# fpga.net
KiCad netlist of a schematic drawn in Altium Designer
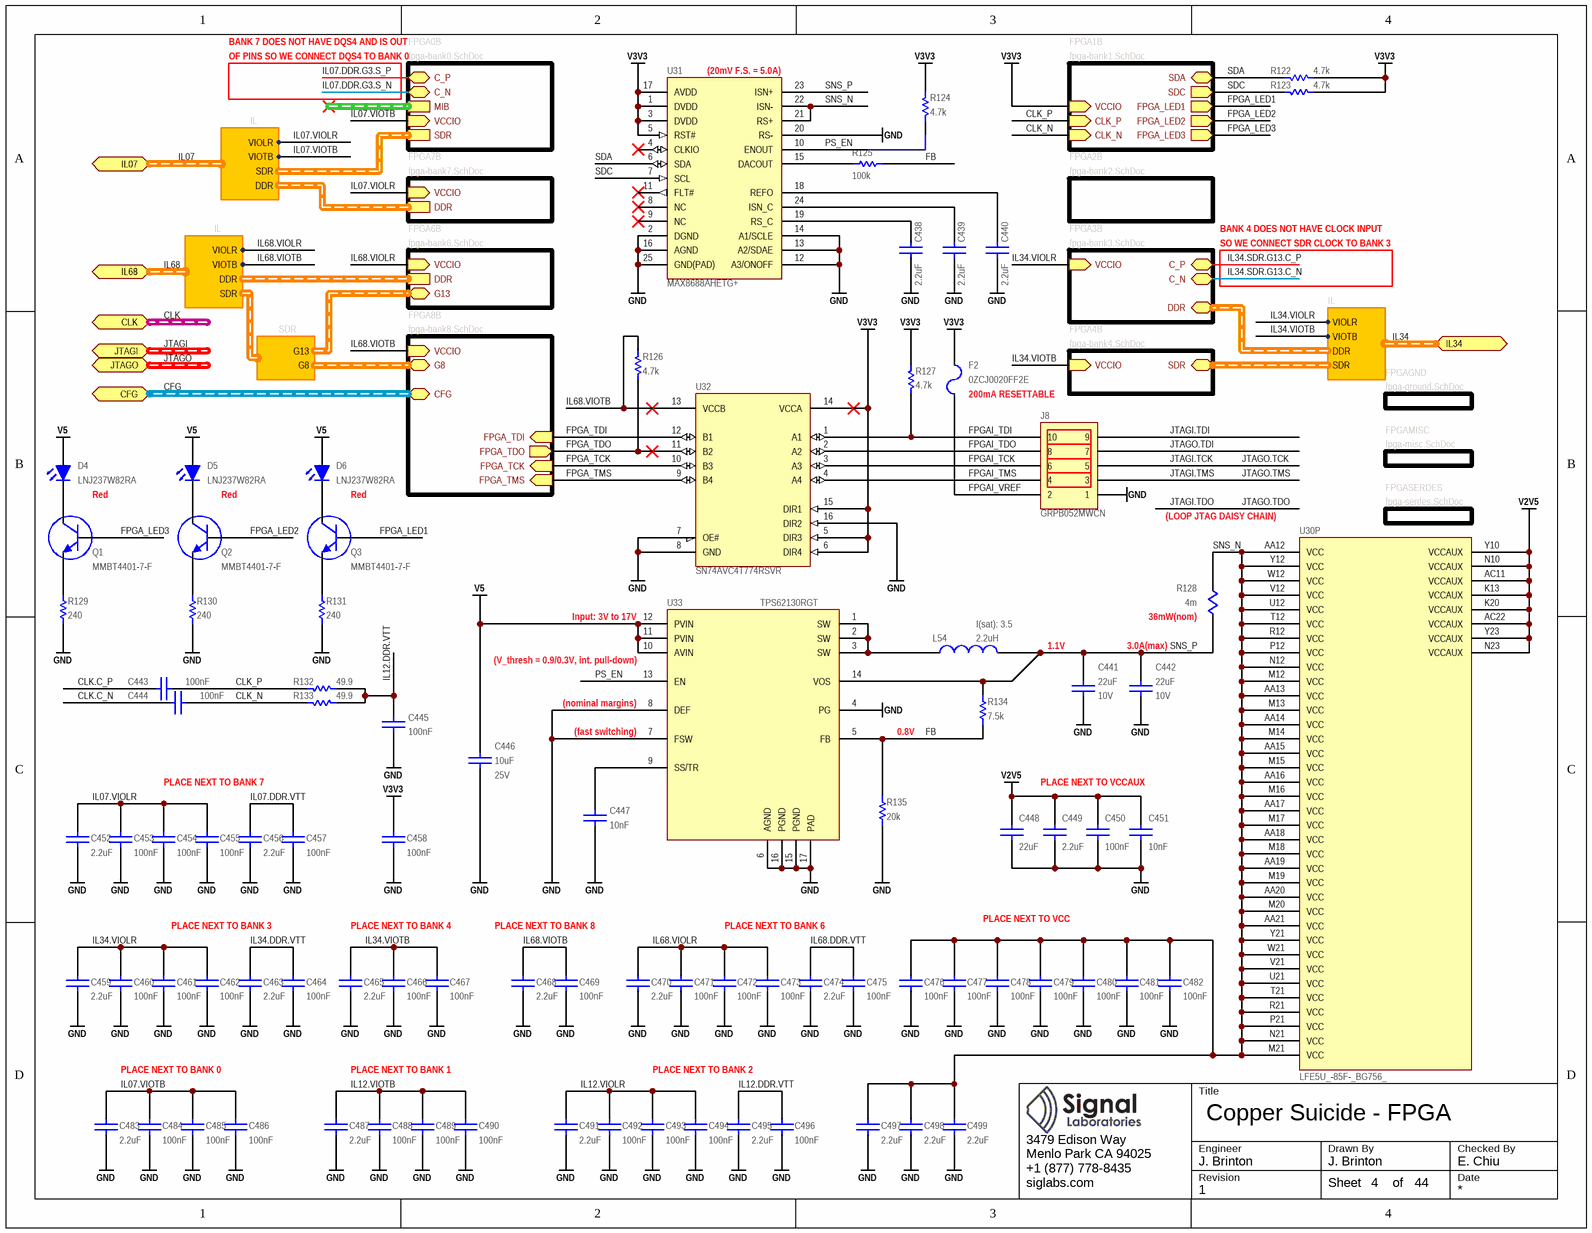
[diagram p0: fpga.SchDoc]

(export (version "E")
  (design (tool "Eeschema 10.0.6"))
  (components
    (comp (ref "C438")
      (value "2.2uF")
      (footprint "CAPC160X80X90L20N")
      (description "Ceramic Capacitor 2.2uF ±20% 10V X7R 0603")
      (fields (field (name "MANUFACTURER") "TDK") (field (name "TOLERANCE") "±20%"))
      (libsource (lib "generic") (part "CAP"))
    )
    (comp (ref "C439")
      (value "2.2uF")
      (footprint "CAPC160X80X90L20N")
      (description "Ceramic Capacitor 2.2uF ±20% 10V X7R 0603")
      (fields (field (name "MANUFACTURER") "TDK") (field (name "TOLERANCE") "±20%"))
      (libsource (lib "generic") (part "CAP"))
    )
    (comp (ref "C440")
      (value "2.2uF")
      (footprint "CAPC160X80X90L20N")
      (description "Ceramic Capacitor 2.2uF ±20% 10V X7R 0603")
      (fields (field (name "MANUFACTURER") "TDK") (field (name "TOLERANCE") "±20%"))
      (libsource (lib "generic") (part "CAP"))
    )
    (comp (ref "C441")
      (value "22uF")
      (footprint "CAPC200X125X145L45N")
      (description "Ceramic Capacitor 22uF ±20% 10V X7S 0805")
      (fields
        (field (name "MANUFACTURER") "TDK")
        (field (name "TOLERANCE") "±20%")
        (field (name "VOLTAGE") "10V")
      )
      (libsource (lib "generic") (part "CAP"))
    )
    (comp (ref "C442")
      (value "22uF")
      (footprint "CAPC200X125X145L45N")
      (description "Ceramic Capacitor 22uF ±20% 10V X7S 0805")
      (fields
        (field (name "MANUFACTURER") "TDK")
        (field (name "TOLERANCE") "±20%")
        (field (name "VOLTAGE") "10V")
      )
      (libsource (lib "generic") (part "CAP"))
    )
    (comp (ref "C443")
      (value "100nF")
      (footprint "CAPC100X50X55L25N")
      (description "Ceramic Capacitor 100nF ±10% 50V X7R 0402")
      (fields (field (name "MANUFACTURER") "Murata") (field (name "TOLERANCE") "±10%"))
      (libsource (lib "generic") (part "CAP"))
    )
    (comp (ref "C444")
      (value "100nF")
      (footprint "CAPC100X50X55L25N")
      (description "Ceramic Capacitor 100nF ±10% 50V X7R 0402")
      (fields (field (name "MANUFACTURER") "Murata") (field (name "TOLERANCE") "±10%"))
      (libsource (lib "generic") (part "CAP"))
    )
    (comp (ref "C445")
      (value "100nF")
      (footprint "CAPC100X50X55L25N")
      (description "Ceramic Capacitor 100nF ±10% 50V X7R 0402")
      (fields (field (name "MANUFACTURER") "Murata") (field (name "TOLERANCE") "±10%"))
      (libsource (lib "generic") (part "CAP"))
    )
    (comp (ref "C446")
      (value "10uF")
      (footprint "CAPC200X125X145L45N")
      (description "Ceramic Capacitor 10uF ±10% 25V X6S 0805")
      (fields
        (field (name "MANUFACTURER") "Murata")
        (field (name "TOLERANCE") "±10%")
        (field (name "VOLTAGE") "25V")
      )
      (libsource (lib "") (part "CAP_1"))
    )
    (comp (ref "C447")
      (value "10nF")
      (footprint "CAPC100X50X55L25N")
      (description "Ceramic Capacitor 10nF ±10% 50V X7R 0402")
      (fields (field (name "MANUFACTURER") "Murata") (field (name "TOLERANCE") "±10%"))
      (libsource (lib "") (part "CAP_1"))
    )
    (comp (ref "C448")
      (value "22uF")
      (footprint "CAPC200X125X145L45N")
      (description "Ceramic Capacitor 22uF ±20% 10V X7S 0805")
      (fields (field (name "MANUFACTURER") "TDK") (field (name "TOLERANCE") "±20%"))
      (libsource (lib "generic") (part "CAP"))
    )
    (comp (ref "C449")
      (value "2.2uF")
      (footprint "CAPC160X80X90L20N")
      (description "Ceramic Capacitor 2.2uF ±20% 10V X7R 0603")
      (fields (field (name "MANUFACTURER") "TDK") (field (name "TOLERANCE") "±20%"))
      (libsource (lib "generic") (part "CAP"))
    )
    (comp (ref "C450")
      (value "100nF")
      (footprint "CAPC100X50X55L25N")
      (description "Ceramic Capacitor 100nF ±10% 50V X7R 0402")
      (fields (field (name "MANUFACTURER") "Murata") (field (name "TOLERANCE") "±10%"))
      (libsource (lib "generic") (part "CAP"))
    )
    (comp (ref "C451")
      (value "10nF")
      (footprint "CAPC100X50X55L25N")
      (description "Ceramic Capacitor 10nF ±10% 50V X7R 0402")
      (fields (field (name "MANUFACTURER") "Murata") (field (name "TOLERANCE") "±10%"))
      (libsource (lib "") (part "CAP_1"))
    )
    (comp (ref "C452")
      (value "2.2uF")
      (footprint "CAPC160X80X90L20N")
      (description "Ceramic Capacitor 2.2uF ±20% 10V X7R 0603")
      (fields (field (name "MANUFACTURER") "TDK") (field (name "TOLERANCE") "±20%"))
      (libsource (lib "generic") (part "CAP"))
    )
    (comp (ref "C453")
      (value "100nF")
      (footprint "CAPC100X50X55L25N")
      (description "Ceramic Capacitor 100nF ±10% 50V X7R 0402")
      (fields (field (name "MANUFACTURER") "Murata") (field (name "TOLERANCE") "±10%"))
      (libsource (lib "generic") (part "CAP"))
    )
    (comp (ref "C454")
      (value "100nF")
      (footprint "CAPC100X50X55L25N")
      (description "Ceramic Capacitor 100nF ±10% 50V X7R 0402")
      (fields (field (name "MANUFACTURER") "Murata") (field (name "TOLERANCE") "±10%"))
      (libsource (lib "generic") (part "CAP"))
    )
    (comp (ref "C455")
      (value "100nF")
      (footprint "CAPC100X50X55L25N")
      (description "Ceramic Capacitor 100nF ±10% 50V X7R 0402")
      (fields (field (name "MANUFACTURER") "Murata") (field (name "TOLERANCE") "±10%"))
      (libsource (lib "generic") (part "CAP"))
    )
    (comp (ref "C456")
      (value "2.2uF")
      (footprint "CAPC160X80X90L20N")
      (description "Ceramic Capacitor 2.2uF ±20% 10V X7R 0603")
      (fields (field (name "MANUFACTURER") "TDK") (field (name "TOLERANCE") "±20%"))
      (libsource (lib "generic") (part "CAP"))
    )
    (comp (ref "C457")
      (value "100nF")
      (footprint "CAPC100X50X55L25N")
      (description "Ceramic Capacitor 100nF ±10% 50V X7R 0402")
      (fields (field (name "MANUFACTURER") "Murata") (field (name "TOLERANCE") "±10%"))
      (libsource (lib "generic") (part "CAP"))
    )
    (comp (ref "C458")
      (value "100nF")
      (footprint "CAPC100X50X55L25N")
      (description "Ceramic Capacitor 100nF ±10% 50V X7R 0402")
      (fields (field (name "MANUFACTURER") "Murata") (field (name "TOLERANCE") "±10%"))
      (libsource (lib "generic") (part "CAP"))
    )
    (comp (ref "C459")
      (value "2.2uF")
      (footprint "CAPC160X80X90L20N")
      (description "Ceramic Capacitor 2.2uF ±20% 10V X7R 0603")
      (fields (field (name "MANUFACTURER") "TDK") (field (name "TOLERANCE") "±20%"))
      (libsource (lib "generic") (part "CAP"))
    )
    (comp (ref "C460")
      (value "100nF")
      (footprint "CAPC100X50X55L25N")
      (description "Ceramic Capacitor 100nF ±10% 50V X7R 0402")
      (fields (field (name "MANUFACTURER") "Murata") (field (name "TOLERANCE") "±10%"))
      (libsource (lib "generic") (part "CAP"))
    )
    (comp (ref "C461")
      (value "100nF")
      (footprint "CAPC100X50X55L25N")
      (description "Ceramic Capacitor 100nF ±10% 50V X7R 0402")
      (fields (field (name "MANUFACTURER") "Murata") (field (name "TOLERANCE") "±10%"))
      (libsource (lib "generic") (part "CAP"))
    )
    (comp (ref "C462")
      (value "100nF")
      (footprint "CAPC100X50X55L25N")
      (description "Ceramic Capacitor 100nF ±10% 50V X7R 0402")
      (fields (field (name "MANUFACTURER") "Murata") (field (name "TOLERANCE") "±10%"))
      (libsource (lib "generic") (part "CAP"))
    )
    (comp (ref "C463")
      (value "2.2uF")
      (footprint "CAPC160X80X90L20N")
      (description "Ceramic Capacitor 2.2uF ±20% 10V X7R 0603")
      (fields (field (name "MANUFACTURER") "TDK") (field (name "TOLERANCE") "±20%"))
      (libsource (lib "generic") (part "CAP"))
    )
    (comp (ref "C464")
      (value "100nF")
      (footprint "CAPC100X50X55L25N")
      (description "Ceramic Capacitor 100nF ±10% 50V X7R 0402")
      (fields (field (name "MANUFACTURER") "Murata") (field (name "TOLERANCE") "±10%"))
      (libsource (lib "generic") (part "CAP"))
    )
    (comp (ref "C465")
      (value "2.2uF")
      (footprint "CAPC160X80X90L20N")
      (description "Ceramic Capacitor 2.2uF ±20% 10V X7R 0603")
      (fields (field (name "MANUFACTURER") "TDK") (field (name "TOLERANCE") "±20%"))
      (libsource (lib "generic") (part "CAP"))
    )
    (comp (ref "C466")
      (value "100nF")
      (footprint "CAPC100X50X55L25N")
      (description "Ceramic Capacitor 100nF ±10% 50V X7R 0402")
      (fields (field (name "MANUFACTURER") "Murata") (field (name "TOLERANCE") "±10%"))
      (libsource (lib "generic") (part "CAP"))
    )
    (comp (ref "C467")
      (value "100nF")
      (footprint "CAPC100X50X55L25N")
      (description "Ceramic Capacitor 100nF ±10% 50V X7R 0402")
      (fields (field (name "MANUFACTURER") "Murata") (field (name "TOLERANCE") "±10%"))
      (libsource (lib "generic") (part "CAP"))
    )
    (comp (ref "C468")
      (value "2.2uF")
      (footprint "CAPC160X80X90L20N")
      (description "Ceramic Capacitor 2.2uF ±20% 10V X7R 0603")
      (fields (field (name "MANUFACTURER") "TDK") (field (name "TOLERANCE") "±20%"))
      (libsource (lib "generic") (part "CAP"))
    )
    (comp (ref "C469")
      (value "100nF")
      (footprint "CAPC100X50X55L25N")
      (description "Ceramic Capacitor 100nF ±10% 50V X7R 0402")
      (fields (field (name "MANUFACTURER") "Murata") (field (name "TOLERANCE") "±10%"))
      (libsource (lib "generic") (part "CAP"))
    )
    (comp (ref "C470")
      (value "2.2uF")
      (footprint "CAPC160X80X90L20N")
      (description "Ceramic Capacitor 2.2uF ±20% 10V X7R 0603")
      (fields (field (name "MANUFACTURER") "TDK") (field (name "TOLERANCE") "±20%"))
      (libsource (lib "generic") (part "CAP"))
    )
    (comp (ref "C471")
      (value "100nF")
      (footprint "CAPC100X50X55L25N")
      (description "Ceramic Capacitor 100nF ±10% 50V X7R 0402")
      (fields (field (name "MANUFACTURER") "Murata") (field (name "TOLERANCE") "±10%"))
      (libsource (lib "generic") (part "CAP"))
    )
    (comp (ref "C472")
      (value "100nF")
      (footprint "CAPC100X50X55L25N")
      (description "Ceramic Capacitor 100nF ±10% 50V X7R 0402")
      (fields (field (name "MANUFACTURER") "Murata") (field (name "TOLERANCE") "±10%"))
      (libsource (lib "generic") (part "CAP"))
    )
    (comp (ref "C473")
      (value "100nF")
      (footprint "CAPC100X50X55L25N")
      (description "Ceramic Capacitor 100nF ±10% 50V X7R 0402")
      (fields (field (name "MANUFACTURER") "Murata") (field (name "TOLERANCE") "±10%"))
      (libsource (lib "generic") (part "CAP"))
    )
    (comp (ref "C474")
      (value "2.2uF")
      (footprint "CAPC160X80X90L20N")
      (description "Ceramic Capacitor 2.2uF ±20% 10V X7R 0603")
      (fields (field (name "MANUFACTURER") "TDK") (field (name "TOLERANCE") "±20%"))
      (libsource (lib "generic") (part "CAP"))
    )
    (comp (ref "C475")
      (value "100nF")
      (footprint "CAPC100X50X55L25N")
      (description "Ceramic Capacitor 100nF ±10% 50V X7R 0402")
      (fields (field (name "MANUFACTURER") "Murata") (field (name "TOLERANCE") "±10%"))
      (libsource (lib "generic") (part "CAP"))
    )
    (comp (ref "C476")
      (value "100nF")
      (footprint "CAPC100X50X55L25N")
      (description "Ceramic Capacitor 100nF ±10% 50V X7R 0402")
      (fields (field (name "MANUFACTURER") "Murata") (field (name "TOLERANCE") "±10%"))
      (libsource (lib "generic") (part "CAP"))
    )
    (comp (ref "C477")
      (value "100nF")
      (footprint "CAPC100X50X55L25N")
      (description "Ceramic Capacitor 100nF ±10% 50V X7R 0402")
      (fields (field (name "MANUFACTURER") "Murata") (field (name "TOLERANCE") "±10%"))
      (libsource (lib "generic") (part "CAP"))
    )
    (comp (ref "C478")
      (value "100nF")
      (footprint "CAPC100X50X55L25N")
      (description "Ceramic Capacitor 100nF ±10% 50V X7R 0402")
      (fields (field (name "MANUFACTURER") "Murata") (field (name "TOLERANCE") "±10%"))
      (libsource (lib "generic") (part "CAP"))
    )
    (comp (ref "C479")
      (value "100nF")
      (footprint "CAPC100X50X55L25N")
      (description "Ceramic Capacitor 100nF ±10% 50V X7R 0402")
      (fields (field (name "MANUFACTURER") "Murata") (field (name "TOLERANCE") "±10%"))
      (libsource (lib "generic") (part "CAP"))
    )
    (comp (ref "C480")
      (value "100nF")
      (footprint "CAPC100X50X55L25N")
      (description "Ceramic Capacitor 100nF ±10% 50V X7R 0402")
      (fields (field (name "MANUFACTURER") "Murata") (field (name "TOLERANCE") "±10%"))
      (libsource (lib "generic") (part "CAP"))
    )
    (comp (ref "C481")
      (value "100nF")
      (footprint "CAPC100X50X55L25N")
      (description "Ceramic Capacitor 100nF ±10% 50V X7R 0402")
      (fields (field (name "MANUFACTURER") "Murata") (field (name "TOLERANCE") "±10%"))
      (libsource (lib "generic") (part "CAP"))
    )
    (comp (ref "C482")
      (value "100nF")
      (footprint "CAPC100X50X55L25N")
      (description "Ceramic Capacitor 100nF ±10% 50V X7R 0402")
      (fields (field (name "MANUFACTURER") "Murata") (field (name "TOLERANCE") "±10%"))
      (libsource (lib "generic") (part "CAP"))
    )
    (comp (ref "C483")
      (value "2.2uF")
      (footprint "CAPC160X80X90L20N")
      (description "Ceramic Capacitor 2.2uF ±20% 10V X7R 0603")
      (fields (field (name "MANUFACTURER") "TDK") (field (name "TOLERANCE") "±20%"))
      (libsource (lib "generic") (part "CAP"))
    )
    (comp (ref "C484")
      (value "100nF")
      (footprint "CAPC100X50X55L25N")
      (description "Ceramic Capacitor 100nF ±10% 50V X7R 0402")
      (fields (field (name "MANUFACTURER") "Murata") (field (name "TOLERANCE") "±10%"))
      (libsource (lib "generic") (part "CAP"))
    )
    (comp (ref "C485")
      (value "100nF")
      (footprint "CAPC100X50X55L25N")
      (description "Ceramic Capacitor 100nF ±10% 50V X7R 0402")
      (fields (field (name "MANUFACTURER") "Murata") (field (name "TOLERANCE") "±10%"))
      (libsource (lib "generic") (part "CAP"))
    )
    (comp (ref "C486")
      (value "100nF")
      (footprint "CAPC100X50X55L25N")
      (description "Ceramic Capacitor 100nF ±10% 50V X7R 0402")
      (fields (field (name "MANUFACTURER") "Murata") (field (name "TOLERANCE") "±10%"))
      (libsource (lib "generic") (part "CAP"))
    )
    (comp (ref "C487")
      (value "2.2uF")
      (footprint "CAPC160X80X90L20N")
      (description "Ceramic Capacitor 2.2uF ±20% 10V X7R 0603")
      (fields (field (name "MANUFACTURER") "TDK") (field (name "TOLERANCE") "±20%"))
      (libsource (lib "generic") (part "CAP"))
    )
    (comp (ref "C488")
      (value "100nF")
      (footprint "CAPC100X50X55L25N")
      (description "Ceramic Capacitor 100nF ±10% 50V X7R 0402")
      (fields (field (name "MANUFACTURER") "Murata") (field (name "TOLERANCE") "±10%"))
      (libsource (lib "generic") (part "CAP"))
    )
    (comp (ref "C489")
      (value "100nF")
      (footprint "CAPC100X50X55L25N")
      (description "Ceramic Capacitor 100nF ±10% 50V X7R 0402")
      (fields (field (name "MANUFACTURER") "Murata") (field (name "TOLERANCE") "±10%"))
      (libsource (lib "generic") (part "CAP"))
    )
    (comp (ref "C490")
      (value "100nF")
      (footprint "CAPC100X50X55L25N")
      (description "Ceramic Capacitor 100nF ±10% 50V X7R 0402")
      (fields (field (name "MANUFACTURER") "Murata") (field (name "TOLERANCE") "±10%"))
      (libsource (lib "generic") (part "CAP"))
    )
    (comp (ref "C491")
      (value "2.2uF")
      (footprint "CAPC160X80X90L20N")
      (description "Ceramic Capacitor 2.2uF ±20% 10V X7R 0603")
      (fields (field (name "MANUFACTURER") "TDK") (field (name "TOLERANCE") "±20%"))
      (libsource (lib "generic") (part "CAP"))
    )
    (comp (ref "C492")
      (value "100nF")
      (footprint "CAPC100X50X55L25N")
      (description "Ceramic Capacitor 100nF ±10% 50V X7R 0402")
      (fields (field (name "MANUFACTURER") "Murata") (field (name "TOLERANCE") "±10%"))
      (libsource (lib "generic") (part "CAP"))
    )
    (comp (ref "C493")
      (value "100nF")
      (footprint "CAPC100X50X55L25N")
      (description "Ceramic Capacitor 100nF ±10% 50V X7R 0402")
      (fields (field (name "MANUFACTURER") "Murata") (field (name "TOLERANCE") "±10%"))
      (libsource (lib "generic") (part "CAP"))
    )
    (comp (ref "C494")
      (value "100nF")
      (footprint "CAPC100X50X55L25N")
      (description "Ceramic Capacitor 100nF ±10% 50V X7R 0402")
      (fields (field (name "MANUFACTURER") "Murata") (field (name "TOLERANCE") "±10%"))
      (libsource (lib "generic") (part "CAP"))
    )
    (comp (ref "C495")
      (value "2.2uF")
      (footprint "CAPC160X80X90L20N")
      (description "Ceramic Capacitor 2.2uF ±20% 10V X7R 0603")
      (fields (field (name "MANUFACTURER") "TDK") (field (name "TOLERANCE") "±20%"))
      (libsource (lib "generic") (part "CAP"))
    )
    (comp (ref "C496")
      (value "100nF")
      (footprint "CAPC100X50X55L25N")
      (description "Ceramic Capacitor 100nF ±10% 50V X7R 0402")
      (fields (field (name "MANUFACTURER") "Murata") (field (name "TOLERANCE") "±10%"))
      (libsource (lib "generic") (part "CAP"))
    )
    (comp (ref "C497")
      (value "2.2uF")
      (footprint "CAPC160X80X90L20N")
      (description "Ceramic Capacitor 2.2uF ±20% 10V X7R 0603")
      (fields (field (name "MANUFACTURER") "TDK") (field (name "TOLERANCE") "±20%"))
      (libsource (lib "generic") (part "CAP"))
    )
    (comp (ref "C498")
      (value "2.2uF")
      (footprint "CAPC160X80X90L20N")
      (description "Ceramic Capacitor 2.2uF ±20% 10V X7R 0603")
      (fields (field (name "MANUFACTURER") "TDK") (field (name "TOLERANCE") "±20%"))
      (libsource (lib "generic") (part "CAP"))
    )
    (comp (ref "C499")
      (value "2.2uF")
      (footprint "CAPC160X80X90L20N")
      (description "Ceramic Capacitor 2.2uF ±20% 10V X7R 0603")
      (fields (field (name "MANUFACTURER") "TDK") (field (name "TOLERANCE") "±20%"))
      (libsource (lib "generic") (part "CAP"))
    )
    (comp (ref "D4")
      (value "LNJ237W82RA")
      (footprint "0603_LED")
      (description "LED, SMT 0603, Color Red, 5mA, 1.85V")
      (fields (field (name "MANUFACTURER") "Panasonic"))
      (libsource (lib "generic") (part "LED0603RD"))
    )
    (comp (ref "D5")
      (value "LNJ237W82RA")
      (footprint "0603_LED")
      (description "LED, SMT 0603, Color Red, 5mA, 1.85V")
      (fields (field (name "MANUFACTURER") "Panasonic"))
      (libsource (lib "generic") (part "LED0603RD"))
    )
    (comp (ref "D6")
      (value "LNJ237W82RA")
      (footprint "0603_LED")
      (description "LED, SMT 0603, Color Red, 5mA, 1.85V")
      (fields (field (name "MANUFACTURER") "Panasonic"))
      (libsource (lib "generic") (part "LED0603RD"))
    )
    (comp (ref "F2")
      (value "0ZCJ0020FF2E")
      (footprint "generic:1206")
      (description "PTC Resettable Fuse, 0.2A, 30V, SMD 1206")
      (fields (field (name "MANUFACTURER") "Bell Fuse"))
      (libsource (lib "bel-fuse") (part "0ZCJ0020FF2E"))
    )
    (comp (ref "J8")
      (value "GRPB052MWCN")
      (footprint "sullins:GRPB052MWCN")
      (description "Male Header, 0.050\" Pitch, 2x5 Position, Right Angle")
      (fields (field (name "MANUFACTURER") "Sullins"))
      (libsource (lib "sullins") (part "GRPB052VWVN"))
    )
    (comp (ref "L54")
      (value "2.2uH")
      (footprint "coilcraft:XFL4020")
      (description "Wirewound Inductor 2.2uH +/-20% 3.5A SMD")
      (fields
        (field (name "MANUFACTURER") "Coilcraft")
        (field (name "I(SAT)") "3.5")
        (field (name "Comment") "XFL4020-222ME")
      )
      (libsource (lib "CamBoard_Pico_70.19K") (part "COIL"))
    )
    (comp (ref "Q1")
      (value "MMBT4401-7-F")
      (footprint "generic:SOT23")
      (description "NPN Small Signal Transistor SMD SOT-23")
      (fields (field (name "MANUFACTURER P/N") "MMBT4401-7-F") (field (name "MANUFACTURER") "Diodes, Inc."))
      (libsource (lib "diodes_inc") (part "MMBT4401-7-F"))
    )
    (comp (ref "Q2")
      (value "MMBT4401-7-F")
      (footprint "generic:SOT23")
      (description "NPN Small Signal Transistor SMD SOT-23")
      (fields (field (name "MANUFACTURER P/N") "MMBT4401-7-F") (field (name "MANUFACTURER") "Diodes, Inc."))
      (libsource (lib "diodes_inc") (part "MMBT4401-7-F"))
    )
    (comp (ref "Q3")
      (value "MMBT4401-7-F")
      (footprint "generic:SOT23")
      (description "NPN Small Signal Transistor SMD SOT-23")
      (fields (field (name "MANUFACTURER P/N") "MMBT4401-7-F") (field (name "MANUFACTURER") "Diodes, Inc."))
      (libsource (lib "diodes_inc") (part "MMBT4401-7-F"))
    )
    (comp (ref "R122")
      (value "4.7k")
      (footprint "RESC1005X40N")
      (description "Thick Film Resistor 4.7k ±1% 0.1W 75V 0402")
      (fields (field (name "TOLERANCE") "±1%") (field (name "MANUFACTURER") "Panasonic"))
      (libsource (lib "generic") (part "RES"))
    )
    (comp (ref "R123")
      (value "4.7k")
      (footprint "RESC1005X40N")
      (description "Thick Film Resistor 4.7k ±1% 0.1W 75V 0402")
      (fields (field (name "TOLERANCE") "±1%") (field (name "MANUFACTURER") "Panasonic"))
      (libsource (lib "generic") (part "RES"))
    )
    (comp (ref "R124")
      (value "4.7k")
      (footprint "RESC1005X40N")
      (description "Thick Film Resistor 4.7k ±1% 0.1W 75V 0402")
      (fields (field (name "TOLERANCE") "±1%") (field (name "MANUFACTURER") "Panasonic"))
      (libsource (lib "generic") (part "RES"))
    )
    (comp (ref "R125")
      (value "100k")
      (footprint "RESC1005X40N")
      (description "Thick Film Resistor 100k ±1% 0.1W 50V 0402")
      (fields (field (name "MANUFACTURER") "Panasonic") (field (name "TOLERANCE") "±1%"))
      (libsource (lib "generic") (part "RES"))
    )
    (comp (ref "R126")
      (value "4.7k")
      (footprint "RESC1005X40N")
      (description "Thick Film Resistor 4.7k ±1% 0.1W 75V 0402")
      (fields (field (name "TOLERANCE") "±1%") (field (name "MANUFACTURER") "Panasonic"))
      (libsource (lib "generic") (part "RES"))
    )
    (comp (ref "R127")
      (value "4.7k")
      (footprint "RESC1005X40N")
      (description "Thick Film Resistor 4.7k ±1% 0.1W 75V 0402")
      (fields (field (name "TOLERANCE") "±1%") (field (name "MANUFACTURER") "Panasonic"))
      (libsource (lib "generic") (part "RES"))
    )
    (comp (ref "R128")
      (value "4m")
      (footprint "RESC3216X80L110N")
      (description "Current Sense Resistor 4mOhm +/-1% SMD 1206")
      (fields (field (name "MANUFACTURER") "Riedon") (field (name "Comment") "CSR1206-0R004F1"))
      (libsource (lib "Kron Library Rev 3") (part "CSR1206-0R001F1"))
    )
    (comp (ref "R129")
      (value "240")
      (footprint "RESC1005X40N")
      (description "Thick Film Resistor 240 ±1% 0.1W 75V 0402")
      (fields (field (name "TOLERANCE") "±1%") (field (name "MANUFACTURER") "Panasonic"))
      (libsource (lib "generic") (part "RES"))
    )
    (comp (ref "R130")
      (value "240")
      (footprint "RESC1005X40N")
      (description "Thick Film Resistor 240 ±1% 0.1W 75V 0402")
      (fields (field (name "TOLERANCE") "±1%") (field (name "MANUFACTURER") "Panasonic"))
      (libsource (lib "generic") (part "RES"))
    )
    (comp (ref "R131")
      (value "240")
      (footprint "RESC1005X40N")
      (description "Thick Film Resistor 240 ±1% 0.1W 75V 0402")
      (fields (field (name "TOLERANCE") "±1%") (field (name "MANUFACTURER") "Panasonic"))
      (libsource (lib "generic") (part "RES"))
    )
    (comp (ref "R132")
      (value "49.9")
      (footprint "RESC1005X40N")
      (description "Thick Film Resistor 49.9 ±1% 0.1W 50V 0402")
      (fields (field (name "TOLERANCE") "±1%") (field (name "MANUFACTURER") "Panasonic"))
      (libsource (lib "generic") (part "RES"))
    )
    (comp (ref "R133")
      (value "49.9")
      (footprint "RESC1005X40N")
      (description "Thick Film Resistor 49.9 ±1% 0.1W 50V 0402")
      (fields (field (name "TOLERANCE") "±1%") (field (name "MANUFACTURER") "Panasonic"))
      (libsource (lib "generic") (part "RES"))
    )
    (comp (ref "R134")
      (value "7.5k")
      (footprint "RESC2012X70N")
      (description "Thin Film Resistor 7.5k ±0.1% 0.125W 100V 0805")
      (fields (field (name "TOLERANCE") "±0.1%") (field (name "MANUFACTURER") "Panasonic"))
      (libsource (lib "generic") (part "RES"))
    )
    (comp (ref "R135")
      (value "20k")
      (footprint "RESC2012X70N")
      (description "Thin Film Resistor 20k ±0.1% 0.125W 100V 0805")
      (fields (field (name "TOLERANCE") "±0.1%") (field (name "MANUFACTURER") "Panasonic"))
      (libsource (lib "generic") (part "RES"))
    )
    (comp (ref "U30")
      (value "LFE5U_-85F-_BG756_")
      (footprint "lattice:caBGA756")
      (description "ECP5 FPGA, 85k LUT, 756-caBGA")
      (fields (field (name "MANUFACTURER") "Lattice Semiconductor"))
      (libsource (lib "lattice") (part "LFE5U_-85F-_BG756_"))
    )
    (comp (ref "U31")
      (value "MAX8688AHETG+")
      (footprint "generic:QFN25P50_400X400X80L40X24T260N")
      (description "Digital Power-Supply Controller/Monitor")
      (fields (field (name "MANUFACTURER") "Maxim Integrated"))
      (libsource (lib "maxim") (part "MAX8688AHETG+"))
    )
    (comp (ref "U32")
      (value "SN74AVC4T774RSVR")
      (footprint "RSV")
      (description "4-Bit Dual-Supply Bus Transceiver")
      (fields (field (name "MANUFACTURER") "Texas Instruments"))
      (libsource (lib "ti") (part "SN74AVC4T774RSVR"))
    )
    (comp (ref "U33")
      (value "TPS62130RGT")
      (footprint "S-PQFP-8N_NOVIA")
      (description "3-17V 3A Step-Down Converter VQFN")
      (fields (field (name "MANUFACTURER") "Texas Instruments"))
      (libsource (lib "ti") (part "TPS62130RGT"))
    )
  )
  (nets
    (net (code "10") (name "/CLK.C_N") (class "Default")
      (node (ref "C444") (pin "2") (pinfunction "2_2") (pintype "passive"))
    )
    (net (code "11") (name "/CLK.C_P") (class "Default")
      (node (ref "C443") (pin "2") (pinfunction "2_2") (pintype "passive"))
    )
    (net (code "12") (name "/CLK_N") (class "Default")
      (node (ref "C444") (pin "1") (pinfunction "1_1") (pintype "passive"))
      (node (ref "R133") (pin "2") (pinfunction "2_2") (pintype "passive"))
    )
    (net (code "13") (name "/CLK_P") (class "Default")
      (node (ref "C443") (pin "1") (pinfunction "1_1") (pintype "passive"))
      (node (ref "R132") (pin "2") (pinfunction "2_2") (pintype "passive"))
    )
    (net (code "14") (name "/FB") (class "Default")
      (node (ref "R125") (pin "2") (pinfunction "2_2") (pintype "passive"))
      (node (ref "R134") (pin "1") (pinfunction "1_1") (pintype "passive"))
      (node (ref "R135") (pin "2") (pinfunction "2_2") (pintype "passive"))
      (node (ref "U33") (pin "5") (pinfunction "FB_5") (pintype "passive"))
    )
    (net (code "15") (name "/FPGAI_TCK") (class "Default")
      (node (ref "J8") (pin "6") (pinfunction "6_6") (pintype "passive"))
      (node (ref "U32") (pin "3") (pinfunction "A3_3") (pintype "bidirectional"))
    )
    (net (code "16") (name "/FPGAI_TDI") (class "Default")
      (node (ref "J8") (pin "10") (pinfunction "10_10") (pintype "passive"))
      (node (ref "R127") (pin "1") (pinfunction "1_1") (pintype "passive"))
      (node (ref "U32") (pin "1") (pinfunction "A1_1") (pintype "bidirectional"))
    )
    (net (code "17") (name "/FPGAI_TDO") (class "Default")
      (node (ref "J8") (pin "8") (pinfunction "8_8") (pintype "passive"))
      (node (ref "U32") (pin "2") (pinfunction "A2_2") (pintype "bidirectional"))
    )
    (net (code "18") (name "/FPGAI_TMS") (class "Default")
      (node (ref "J8") (pin "4") (pinfunction "4_4") (pintype "passive"))
      (node (ref "U32") (pin "4") (pinfunction "A4_4") (pintype "bidirectional"))
    )
    (net (code "19") (name "/FPGAI_VREF") (class "Default")
      (node (ref "F2") (pin "2") (pinfunction "2_2") (pintype "passive"))
      (node (ref "J8") (pin "2") (pinfunction "2_2") (pintype "passive"))
    )
    (net (code "20") (name "/FPGA_LED1") (class "Default")
      (node (ref "Q3") (pin "1") (pinfunction "B_1") (pintype "passive"))
    )
    (net (code "21") (name "/FPGA_LED2") (class "Default")
      (node (ref "Q2") (pin "1") (pinfunction "B_1") (pintype "passive"))
    )
    (net (code "22") (name "/FPGA_LED3") (class "Default")
      (node (ref "Q1") (pin "1") (pinfunction "B_1") (pintype "passive"))
    )
    (net (code "23") (name "/FPGA_TCK") (class "Default")
      (node (ref "U32") (pin "10") (pinfunction "B3_10") (pintype "bidirectional"))
    )
    (net (code "24") (name "/FPGA_TDI") (class "Default")
      (node (ref "U32") (pin "12") (pinfunction "B1_12") (pintype "bidirectional"))
    )
    (net (code "25") (name "/FPGA_TDO") (class "Default")
      (node (ref "R126") (pin "1") (pinfunction "1_1") (pintype "passive"))
      (node (ref "U32") (pin "11") (pinfunction "B2_11") (pintype "bidirectional"))
    )
    (net (code "26") (name "/FPGA_TMS") (class "Default")
      (node (ref "U32") (pin "9") (pinfunction "B4_9") (pintype "bidirectional"))
    )
    (net (code "29") (name "/IL07.DDR.VTT") (class "Default")
      (node (ref "C456") (pin "2") (pinfunction "2_2") (pintype "passive"))
      (node (ref "C457") (pin "2") (pinfunction "2_2") (pintype "passive"))
    )
    (net (code "30") (name "/IL07.VIOLR") (class "Default")
      (node (ref "C452") (pin "2") (pinfunction "2_2") (pintype "passive"))
      (node (ref "C453") (pin "2") (pinfunction "2_2") (pintype "passive"))
      (node (ref "C454") (pin "2") (pinfunction "2_2") (pintype "passive"))
      (node (ref "C455") (pin "2") (pinfunction "2_2") (pintype "passive"))
    )
    (net (code "31") (name "/IL07.VIOTB") (class "Default")
      (node (ref "C483") (pin "2") (pinfunction "2_2") (pintype "passive"))
      (node (ref "C484") (pin "2") (pinfunction "2_2") (pintype "passive"))
      (node (ref "C485") (pin "2") (pinfunction "2_2") (pintype "passive"))
      (node (ref "C486") (pin "2") (pinfunction "2_2") (pintype "passive"))
    )
    (net (code "32") (name "/IL12.DDR.VTT") (class "Default")
      (node (ref "C445") (pin "2") (pinfunction "2_2") (pintype "passive"))
      (node (ref "C495") (pin "2") (pinfunction "2_2") (pintype "passive"))
      (node (ref "C496") (pin "2") (pinfunction "2_2") (pintype "passive"))
      (node (ref "R132") (pin "1") (pinfunction "1_1") (pintype "passive"))
      (node (ref "R133") (pin "1") (pinfunction "1_1") (pintype "passive"))
    )
    (net (code "33") (name "/IL12.VIOLR") (class "Default")
      (node (ref "C491") (pin "2") (pinfunction "2_2") (pintype "passive"))
      (node (ref "C492") (pin "2") (pinfunction "2_2") (pintype "passive"))
      (node (ref "C493") (pin "2") (pinfunction "2_2") (pintype "passive"))
      (node (ref "C494") (pin "2") (pinfunction "2_2") (pintype "passive"))
    )
    (net (code "34") (name "/IL12.VIOTB") (class "Default")
      (node (ref "C487") (pin "2") (pinfunction "2_2") (pintype "passive"))
      (node (ref "C488") (pin "2") (pinfunction "2_2") (pintype "passive"))
      (node (ref "C489") (pin "2") (pinfunction "2_2") (pintype "passive"))
      (node (ref "C490") (pin "2") (pinfunction "2_2") (pintype "passive"))
    )
    (net (code "35") (name "/IL34.DDR.VTT") (class "Default")
      (node (ref "C463") (pin "2") (pinfunction "2_2") (pintype "passive"))
      (node (ref "C464") (pin "2") (pinfunction "2_2") (pintype "passive"))
    )
    (net (code "38") (name "/IL34.VIOLR") (class "Default")
      (node (ref "C459") (pin "2") (pinfunction "2_2") (pintype "passive"))
      (node (ref "C460") (pin "2") (pinfunction "2_2") (pintype "passive"))
      (node (ref "C461") (pin "2") (pinfunction "2_2") (pintype "passive"))
      (node (ref "C462") (pin "2") (pinfunction "2_2") (pintype "passive"))
    )
    (net (code "39") (name "/IL34.VIOTB") (class "Default")
      (node (ref "C465") (pin "2") (pinfunction "2_2") (pintype "passive"))
      (node (ref "C466") (pin "2") (pinfunction "2_2") (pintype "passive"))
      (node (ref "C467") (pin "2") (pinfunction "2_2") (pintype "passive"))
    )
    (net (code "40") (name "/IL68.DDR.VTT") (class "Default")
      (node (ref "C474") (pin "2") (pinfunction "2_2") (pintype "passive"))
      (node (ref "C475") (pin "2") (pinfunction "2_2") (pintype "passive"))
    )
    (net (code "41") (name "/IL68.VIOLR") (class "Default")
      (node (ref "C470") (pin "2") (pinfunction "2_2") (pintype "passive"))
      (node (ref "C471") (pin "2") (pinfunction "2_2") (pintype "passive"))
      (node (ref "C472") (pin "2") (pinfunction "2_2") (pintype "passive"))
      (node (ref "C473") (pin "2") (pinfunction "2_2") (pintype "passive"))
    )
    (net (code "42") (name "/IL68.VIOTB") (class "Default")
      (node (ref "C468") (pin "2") (pinfunction "2_2") (pintype "passive"))
      (node (ref "C469") (pin "2") (pinfunction "2_2") (pintype "passive"))
      (node (ref "R126") (pin "2") (pinfunction "2_2") (pintype "passive"))
      (node (ref "U32") (pin "13") (pinfunction "VCCB_13") (pintype "power_in"))
    )
    (net (code "43") (name "/JTAGI.TCK") (class "Default")
      (node (ref "J8") (pin "5") (pinfunction "5_5") (pintype "passive"))
    )
    (net (code "44") (name "/JTAGI.TDI") (class "Default")
      (node (ref "J8") (pin "9") (pinfunction "9_9") (pintype "passive"))
    )
    (net (code "46") (name "/JTAGI.TMS") (class "Default")
      (node (ref "J8") (pin "3") (pinfunction "3_3") (pintype "passive"))
    )
    (net (code "47") (name "/JTAGO.TDI") (class "Default")
      (node (ref "J8") (pin "7") (pinfunction "7_7") (pintype "passive"))
    )
    (net (code "49") (name "/PS_EN") (class "Default")
      (node (ref "R124") (pin "1") (pinfunction "1_1") (pintype "passive"))
      (node (ref "U31") (pin "10") (pinfunction "ENOUT_10") (pintype "passive"))
      (node (ref "U33") (pin "13") (pinfunction "EN_13") (pintype "passive"))
    )
    (net (code "50") (name "/SDA") (class "Default")
      (node (ref "R122") (pin "2") (pinfunction "2_2") (pintype "passive"))
      (node (ref "U31") (pin "6") (pinfunction "SDA_6") (pintype "bidirectional"))
    )
    (net (code "51") (name "/SDC") (class "Default")
      (node (ref "R123") (pin "2") (pinfunction "2_2") (pintype "passive"))
      (node (ref "U31") (pin "7") (pinfunction "SCL_7") (pintype "input"))
    )
    (net (code "52") (name "/SNS_N") (class "Default")
      (node (ref "C476") (pin "2") (pinfunction "2_2") (pintype "passive"))
      (node (ref "C477") (pin "2") (pinfunction "2_2") (pintype "passive"))
      (node (ref "C478") (pin "2") (pinfunction "2_2") (pintype "passive"))
      (node (ref "C479") (pin "2") (pinfunction "2_2") (pintype "passive"))
      (node (ref "C480") (pin "2") (pinfunction "2_2") (pintype "passive"))
      (node (ref "C481") (pin "2") (pinfunction "2_2") (pintype "passive"))
      (node (ref "C482") (pin "2") (pinfunction "2_2") (pintype "passive"))
      (node (ref "C497") (pin "2") (pinfunction "2_2") (pintype "passive"))
      (node (ref "C498") (pin "2") (pinfunction "2_2") (pintype "passive"))
      (node (ref "C499") (pin "2") (pinfunction "2_2") (pintype "passive"))
      (node (ref "R128") (pin "2") (pintype "passive"))
      (node (ref "U30") (pin "AA12") (pinfunction "VCC_AA12") (pintype "power_in"))
      (node (ref "U30") (pin "AA13") (pinfunction "VCC_AA13") (pintype "power_in"))
      (node (ref "U30") (pin "AA14") (pinfunction "VCC_AA14") (pintype "power_in"))
      (node (ref "U30") (pin "AA15") (pinfunction "VCC_AA15") (pintype "power_in"))
      (node (ref "U30") (pin "AA16") (pinfunction "VCC_AA16") (pintype "power_in"))
      (node (ref "U30") (pin "AA17") (pinfunction "VCC_AA17") (pintype "power_in"))
      (node (ref "U30") (pin "AA18") (pinfunction "VCC_AA18") (pintype "power_in"))
      (node (ref "U30") (pin "AA19") (pinfunction "VCC_AA19") (pintype "power_in"))
      (node (ref "U30") (pin "AA20") (pinfunction "VCC_AA20") (pintype "power_in"))
      (node (ref "U30") (pin "AA21") (pinfunction "VCC_AA21") (pintype "power_in"))
      (node (ref "U30") (pin "M12") (pinfunction "VCC_M12") (pintype "power_in"))
      (node (ref "U30") (pin "M13") (pinfunction "VCC_M13") (pintype "power_in"))
      (node (ref "U30") (pin "M14") (pinfunction "VCC_M14") (pintype "power_in"))
      (node (ref "U30") (pin "M15") (pinfunction "VCC_M15") (pintype "power_in"))
      (node (ref "U30") (pin "M16") (pinfunction "VCC_M16") (pintype "power_in"))
      (node (ref "U30") (pin "M17") (pinfunction "VCC_M17") (pintype "power_in"))
      (node (ref "U30") (pin "M18") (pinfunction "VCC_M18") (pintype "power_in"))
      (node (ref "U30") (pin "M19") (pinfunction "VCC_M19") (pintype "power_in"))
      (node (ref "U30") (pin "M20") (pinfunction "VCC_M20") (pintype "power_in"))
      (node (ref "U30") (pin "M21") (pinfunction "VCC_M21") (pintype "power_in"))
      (node (ref "U30") (pin "N12") (pinfunction "VCC_N12") (pintype "power_in"))
      (node (ref "U30") (pin "N21") (pinfunction "VCC_N21") (pintype "power_in"))
      (node (ref "U30") (pin "P12") (pinfunction "VCC_P12") (pintype "power_in"))
      (node (ref "U30") (pin "P21") (pinfunction "VCC_P21") (pintype "power_in"))
      (node (ref "U30") (pin "R12") (pinfunction "VCC_R12") (pintype "power_in"))
      (node (ref "U30") (pin "R21") (pinfunction "VCC_R21") (pintype "power_in"))
      (node (ref "U30") (pin "T12") (pinfunction "VCC_T12") (pintype "power_in"))
      (node (ref "U30") (pin "T21") (pinfunction "VCC_T21") (pintype "power_in"))
      (node (ref "U30") (pin "U12") (pinfunction "VCC_U12") (pintype "power_in"))
      (node (ref "U30") (pin "U21") (pinfunction "VCC_U21") (pintype "power_in"))
      (node (ref "U30") (pin "V12") (pinfunction "VCC_V12") (pintype "power_in"))
      (node (ref "U30") (pin "V21") (pinfunction "VCC_V21") (pintype "power_in"))
      (node (ref "U30") (pin "W12") (pinfunction "VCC_W12") (pintype "power_in"))
      (node (ref "U30") (pin "W21") (pinfunction "VCC_W21") (pintype "power_in"))
      (node (ref "U30") (pin "Y12") (pinfunction "VCC_Y12") (pintype "power_in"))
      (node (ref "U30") (pin "Y21") (pinfunction "VCC_Y21") (pintype "power_in"))
      (node (ref "U31") (pin "21") (pinfunction "RS+_21") (pintype "passive"))
      (node (ref "U31") (pin "22") (pinfunction "ISN-_22") (pintype "passive"))
    )
    (net (code "53") (name "/SNS_P") (class "Default")
      (node (ref "C441") (pin "2") (pinfunction "2_2") (pintype "passive"))
      (node (ref "C442") (pin "2") (pinfunction "2_2") (pintype "passive"))
      (node (ref "L54") (pin "2") (pinfunction "2_2") (pintype "passive"))
      (node (ref "R128") (pin "1") (pintype "passive"))
      (node (ref "R134") (pin "2") (pinfunction "2_2") (pintype "passive"))
      (node (ref "U31") (pin "23") (pinfunction "ISN+_23") (pintype "passive"))
      (node (ref "U33") (pin "14") (pinfunction "VOS_14") (pintype "passive"))
    )
    (net (code "63") (name "GND") (class "Default")
      (node (ref "C438") (pin "1") (pinfunction "1_1") (pintype "passive"))
      (node (ref "C439") (pin "1") (pinfunction "1_1") (pintype "passive"))
      (node (ref "C440") (pin "1") (pinfunction "1_1") (pintype "passive"))
      (node (ref "C441") (pin "1") (pinfunction "1_1") (pintype "passive"))
      (node (ref "C442") (pin "1") (pinfunction "1_1") (pintype "passive"))
      (node (ref "C445") (pin "1") (pinfunction "1_1") (pintype "passive"))
      (node (ref "C446") (pin "1") (pinfunction "1_1") (pintype "passive"))
      (node (ref "C447") (pin "2") (pinfunction "2_2") (pintype "passive"))
      (node (ref "C448") (pin "1") (pinfunction "1_1") (pintype "passive"))
      (node (ref "C449") (pin "1") (pinfunction "1_1") (pintype "passive"))
      (node (ref "C450") (pin "1") (pinfunction "1_1") (pintype "passive"))
      (node (ref "C451") (pin "2") (pinfunction "2_2") (pintype "passive"))
      (node (ref "C452") (pin "1") (pinfunction "1_1") (pintype "passive"))
      (node (ref "C453") (pin "1") (pinfunction "1_1") (pintype "passive"))
      (node (ref "C454") (pin "1") (pinfunction "1_1") (pintype "passive"))
      (node (ref "C455") (pin "1") (pinfunction "1_1") (pintype "passive"))
      (node (ref "C456") (pin "1") (pinfunction "1_1") (pintype "passive"))
      (node (ref "C457") (pin "1") (pinfunction "1_1") (pintype "passive"))
      (node (ref "C458") (pin "1") (pinfunction "1_1") (pintype "passive"))
      (node (ref "C459") (pin "1") (pinfunction "1_1") (pintype "passive"))
      (node (ref "C460") (pin "1") (pinfunction "1_1") (pintype "passive"))
      (node (ref "C461") (pin "1") (pinfunction "1_1") (pintype "passive"))
      (node (ref "C462") (pin "1") (pinfunction "1_1") (pintype "passive"))
      (node (ref "C463") (pin "1") (pinfunction "1_1") (pintype "passive"))
      (node (ref "C464") (pin "1") (pinfunction "1_1") (pintype "passive"))
      (node (ref "C465") (pin "1") (pinfunction "1_1") (pintype "passive"))
      (node (ref "C466") (pin "1") (pinfunction "1_1") (pintype "passive"))
      (node (ref "C467") (pin "1") (pinfunction "1_1") (pintype "passive"))
      (node (ref "C468") (pin "1") (pinfunction "1_1") (pintype "passive"))
      (node (ref "C469") (pin "1") (pinfunction "1_1") (pintype "passive"))
      (node (ref "C470") (pin "1") (pinfunction "1_1") (pintype "passive"))
      (node (ref "C471") (pin "1") (pinfunction "1_1") (pintype "passive"))
      (node (ref "C472") (pin "1") (pinfunction "1_1") (pintype "passive"))
      (node (ref "C473") (pin "1") (pinfunction "1_1") (pintype "passive"))
      (node (ref "C474") (pin "1") (pinfunction "1_1") (pintype "passive"))
      (node (ref "C475") (pin "1") (pinfunction "1_1") (pintype "passive"))
      (node (ref "C476") (pin "1") (pinfunction "1_1") (pintype "passive"))
      (node (ref "C477") (pin "1") (pinfunction "1_1") (pintype "passive"))
      (node (ref "C478") (pin "1") (pinfunction "1_1") (pintype "passive"))
      (node (ref "C479") (pin "1") (pinfunction "1_1") (pintype "passive"))
      (node (ref "C480") (pin "1") (pinfunction "1_1") (pintype "passive"))
      (node (ref "C481") (pin "1") (pinfunction "1_1") (pintype "passive"))
      (node (ref "C482") (pin "1") (pinfunction "1_1") (pintype "passive"))
      (node (ref "C483") (pin "1") (pinfunction "1_1") (pintype "passive"))
      (node (ref "C484") (pin "1") (pinfunction "1_1") (pintype "passive"))
      (node (ref "C485") (pin "1") (pinfunction "1_1") (pintype "passive"))
      (node (ref "C486") (pin "1") (pinfunction "1_1") (pintype "passive"))
      (node (ref "C487") (pin "1") (pinfunction "1_1") (pintype "passive"))
      (node (ref "C488") (pin "1") (pinfunction "1_1") (pintype "passive"))
      (node (ref "C489") (pin "1") (pinfunction "1_1") (pintype "passive"))
      (node (ref "C490") (pin "1") (pinfunction "1_1") (pintype "passive"))
      (node (ref "C491") (pin "1") (pinfunction "1_1") (pintype "passive"))
      (node (ref "C492") (pin "1") (pinfunction "1_1") (pintype "passive"))
      (node (ref "C493") (pin "1") (pinfunction "1_1") (pintype "passive"))
      (node (ref "C494") (pin "1") (pinfunction "1_1") (pintype "passive"))
      (node (ref "C495") (pin "1") (pinfunction "1_1") (pintype "passive"))
      (node (ref "C496") (pin "1") (pinfunction "1_1") (pintype "passive"))
      (node (ref "C497") (pin "1") (pinfunction "1_1") (pintype "passive"))
      (node (ref "C498") (pin "1") (pinfunction "1_1") (pintype "passive"))
      (node (ref "C499") (pin "1") (pinfunction "1_1") (pintype "passive"))
      (node (ref "J8") (pin "1") (pinfunction "1_1") (pintype "passive"))
      (node (ref "R129") (pin "2") (pinfunction "2_2") (pintype "passive"))
      (node (ref "R130") (pin "2") (pinfunction "2_2") (pintype "passive"))
      (node (ref "R131") (pin "2") (pinfunction "2_2") (pintype "passive"))
      (node (ref "R135") (pin "1") (pinfunction "1_1") (pintype "passive"))
      (node (ref "U31") (pin "12") (pinfunction "A3/ONOFF_12") (pintype "passive"))
      (node (ref "U31") (pin "13") (pinfunction "A2/SDAE_13") (pintype "passive"))
      (node (ref "U31") (pin "14") (pinfunction "A1/SCLE_14") (pintype "passive"))
      (node (ref "U31") (pin "16") (pinfunction "AGND_16") (pintype "power_in"))
      (node (ref "U31") (pin "2") (pinfunction "DGND_2") (pintype "power_in"))
      (node (ref "U31") (pin "20") (pinfunction "RS-_20") (pintype "passive"))
      (node (ref "U31") (pin "25") (pinfunction "GND(PAD)_25") (pintype "power_in"))
      (node (ref "U32") (pin "16") (pinfunction "DIR2_16") (pintype "input"))
      (node (ref "U32") (pin "7") (pinfunction "OE#_7") (pintype "passive"))
      (node (ref "U32") (pin "8") (pinfunction "GND_8") (pintype "power_in"))
      (node (ref "U33") (pin "15") (pinfunction "PGND_15") (pintype "passive"))
      (node (ref "U33") (pin "16") (pinfunction "PGND_16") (pintype "passive"))
      (node (ref "U33") (pin "17") (pinfunction "PAD_17") (pintype "passive"))
      (node (ref "U33") (pin "4") (pinfunction "PG_4") (pintype "passive"))
      (node (ref "U33") (pin "6") (pinfunction "AGND_6") (pintype "passive"))
      (node (ref "U33") (pin "7") (pinfunction "FSW_7") (pintype "passive"))
      (node (ref "U33") (pin "8") (pinfunction "DEF_8") (pintype "passive"))
    )
    (net (code "64") (name "Net-(D4-K)") (class "Default")
      (node (ref "D4") (pin "2") (pinfunction "K_2") (pintype "passive"))
      (node (ref "Q1") (pin "3") (pinfunction "C_3") (pintype "passive"))
    )
    (net (code "65") (name "Net-(D5-K)") (class "Default")
      (node (ref "D5") (pin "2") (pinfunction "K_2") (pintype "passive"))
      (node (ref "Q2") (pin "3") (pinfunction "C_3") (pintype "passive"))
    )
    (net (code "66") (name "Net-(D6-K)") (class "Default")
      (node (ref "D6") (pin "2") (pinfunction "K_2") (pintype "passive"))
      (node (ref "Q3") (pin "3") (pinfunction "C_3") (pintype "passive"))
    )
    (net (code "67") (name "Net-(L54-Pad1)") (class "Default")
      (node (ref "L54") (pin "1") (pinfunction "1_1") (pintype "passive"))
      (node (ref "U33") (pin "1") (pinfunction "SW_1") (pintype "passive"))
      (node (ref "U33") (pin "2") (pinfunction "SW_2") (pintype "passive"))
      (node (ref "U33") (pin "3") (pinfunction "SW_3") (pintype "passive"))
    )
    (net (code "68") (name "Net-(Q1-E)") (class "Default")
      (node (ref "Q1") (pin "2") (pinfunction "E_2") (pintype "passive"))
      (node (ref "R129") (pin "1") (pinfunction "1_1") (pintype "passive"))
    )
    (net (code "69") (name "Net-(Q2-E)") (class "Default")
      (node (ref "Q2") (pin "2") (pinfunction "E_2") (pintype "passive"))
      (node (ref "R130") (pin "1") (pinfunction "1_1") (pintype "passive"))
    )
    (net (code "70") (name "Net-(Q3-E)") (class "Default")
      (node (ref "Q3") (pin "2") (pinfunction "E_2") (pintype "passive"))
      (node (ref "R131") (pin "1") (pinfunction "1_1") (pintype "passive"))
    )
    (net (code "71") (name "Net-(U31-DACOUT)") (class "Default")
      (node (ref "R125") (pin "1") (pinfunction "1_1") (pintype "passive"))
      (node (ref "U31") (pin "15") (pinfunction "DACOUT_15") (pintype "passive"))
    )
    (net (code "72") (name "Net-(U31-ISN_C)") (class "Default")
      (node (ref "C439") (pin "2") (pinfunction "2_2") (pintype "passive"))
      (node (ref "U31") (pin "24") (pinfunction "ISN_C_24") (pintype "passive"))
    )
    (net (code "73") (name "Net-(U31-REFO)") (class "Default")
      (node (ref "C440") (pin "2") (pinfunction "2_2") (pintype "passive"))
      (node (ref "U31") (pin "18") (pinfunction "REFO_18") (pintype "passive"))
    )
    (net (code "74") (name "Net-(U31-RS_C)") (class "Default")
      (node (ref "C438") (pin "2") (pinfunction "2_2") (pintype "passive"))
      (node (ref "U31") (pin "19") (pinfunction "RS_C_19") (pintype "passive"))
    )
    (net (code "75") (name "Net-(U33-SS{slash}TR)") (class "Default")
      (node (ref "C447") (pin "1") (pinfunction "1_1") (pintype "passive"))
      (node (ref "U33") (pin "9") (pinfunction "SS/TR_9") (pintype "passive"))
    )
    (net (code "76") (name "V2V5") (class "Default")
      (node (ref "C448") (pin "2") (pinfunction "2_2") (pintype "passive"))
      (node (ref "C449") (pin "2") (pinfunction "2_2") (pintype "passive"))
      (node (ref "C450") (pin "2") (pinfunction "2_2") (pintype "passive"))
      (node (ref "C451") (pin "1") (pinfunction "1_1") (pintype "passive"))
      (node (ref "U30") (pin "AC11") (pinfunction "VCCAUX_AC11") (pintype "power_in"))
      (node (ref "U30") (pin "AC22") (pinfunction "VCCAUX_AC22") (pintype "power_in"))
      (node (ref "U30") (pin "K13") (pinfunction "VCCAUX_K13") (pintype "power_in"))
      (node (ref "U30") (pin "K20") (pinfunction "VCCAUX_K20") (pintype "power_in"))
      (node (ref "U30") (pin "N10") (pinfunction "VCCAUX_N10") (pintype "power_in"))
      (node (ref "U30") (pin "N23") (pinfunction "VCCAUX_N23") (pintype "power_in"))
      (node (ref "U30") (pin "Y10") (pinfunction "VCCAUX_Y10") (pintype "power_in"))
      (node (ref "U30") (pin "Y23") (pinfunction "VCCAUX_Y23") (pintype "power_in"))
    )
    (net (code "77") (name "V3V3") (class "Default")
      (node (ref "C458") (pin "2") (pinfunction "2_2") (pintype "passive"))
      (node (ref "F2") (pin "1") (pinfunction "1_1") (pintype "passive"))
      (node (ref "R122") (pin "1") (pinfunction "1_1") (pintype "passive"))
      (node (ref "R123") (pin "1") (pinfunction "1_1") (pintype "passive"))
      (node (ref "R124") (pin "2") (pinfunction "2_2") (pintype "passive"))
      (node (ref "R127") (pin "2") (pinfunction "2_2") (pintype "passive"))
      (node (ref "U31") (pin "1") (pinfunction "DVDD_1") (pintype "power_in"))
      (node (ref "U31") (pin "17") (pinfunction "AVDD_17") (pintype "power_in"))
      (node (ref "U31") (pin "3") (pinfunction "DVDD_3") (pintype "power_in"))
      (node (ref "U31") (pin "5") (pinfunction "RST#_5") (pintype "input"))
      (node (ref "U32") (pin "14") (pinfunction "VCCA_14") (pintype "power_in"))
      (node (ref "U32") (pin "15") (pinfunction "DIR1_15") (pintype "input"))
      (node (ref "U32") (pin "5") (pinfunction "DIR3_5") (pintype "input"))
      (node (ref "U32") (pin "6") (pinfunction "DIR4_6") (pintype "input"))
    )
    (net (code "78") (name "V5") (class "Default")
      (node (ref "C446") (pin "2") (pinfunction "2_2") (pintype "passive"))
      (node (ref "D4") (pin "1") (pinfunction "A_1") (pintype "passive"))
      (node (ref "D5") (pin "1") (pinfunction "A_1") (pintype "passive"))
      (node (ref "D6") (pin "1") (pinfunction "A_1") (pintype "passive"))
      (node (ref "U33") (pin "10") (pinfunction "AVIN_10") (pintype "passive"))
      (node (ref "U33") (pin "11") (pinfunction "PVIN_11") (pintype "passive"))
      (node (ref "U33") (pin "12") (pinfunction "PVIN_12") (pintype "passive"))
    )
    (net (code "79") (name "unconnected-(U31-CLKIO-Pad4)") (class "Default")
      (node (ref "U31") (pin "4") (pinfunction "CLKIO_4") (pintype "bidirectional+no_connect"))
    )
    (net (code "80") (name "unconnected-(U31-FLT#-Pad11)") (class "Default")
      (node (ref "U31") (pin "11") (pinfunction "FLT#_11") (pintype "output+no_connect"))
    )
    (net (code "81") (name "unconnected-(U31-NC-Pad8)") (class "Default")
      (node (ref "U31") (pin "8") (pinfunction "NC_8") (pintype "passive+no_connect"))
    )
    (net (code "82") (name "unconnected-(U31-NC-Pad9)") (class "Default")
      (node (ref "U31") (pin "9") (pinfunction "NC_9") (pintype "passive+no_connect"))
    )
  )
)
